# BV100011_ControlTopLevel.net
KiCad netlist of a schematic drawn in Altium Designer
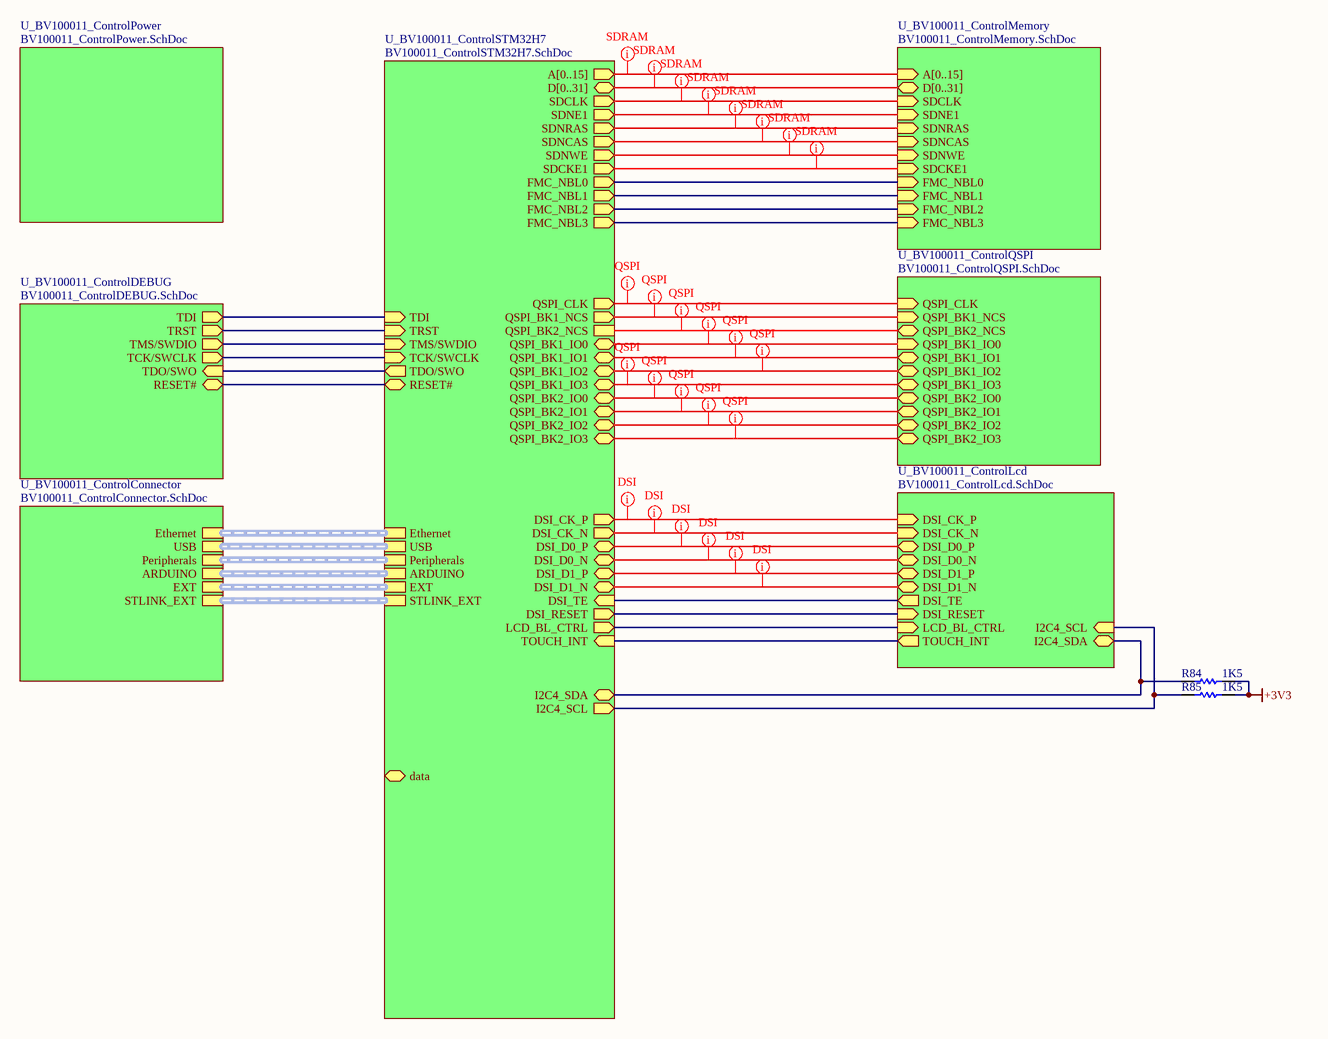
[diagram p0: BV100011_ControlTopLevel.SchDoc]

(export (version "E")
  (design (tool "Eeschema 10.0.6"))
  (components
    (comp (ref "R84")
      (value "1K5")
      (footprint "R0603")
      (description "Resistor")
      (fields (field (name "PUBLISHER") "Altium Limited"))
      (libsource (lib "Miscellaneous Devices") (part "Res1"))
    )
    (comp (ref "R85")
      (value "1K5")
      (footprint "R0603")
      (description "Resistor")
      (fields (field (name "PUBLISHER") "Altium Limited"))
      (libsource (lib "Miscellaneous Devices") (part "Res1"))
    )
  )
  (nets
    (net (code "1") (name "+3V3") (class "Default")
      (node (ref "R84") (pin "1") (pinfunction "1_1") (pintype "passive"))
      (node (ref "R85") (pin "1") (pinfunction "1_1") (pintype "passive"))
    )
    (net (code "19") (name "/I2C4_SCL") (class "Default")
      (node (ref "R85") (pin "2") (pinfunction "2_2") (pintype "passive"))
    )
    (net (code "20") (name "/I2C4_SDA") (class "Default")
      (node (ref "R84") (pin "2") (pinfunction "2_2") (pintype "passive"))
    )
  )
)
